# power_supply.net
KiCad netlist of a schematic drawn in Altium Designer
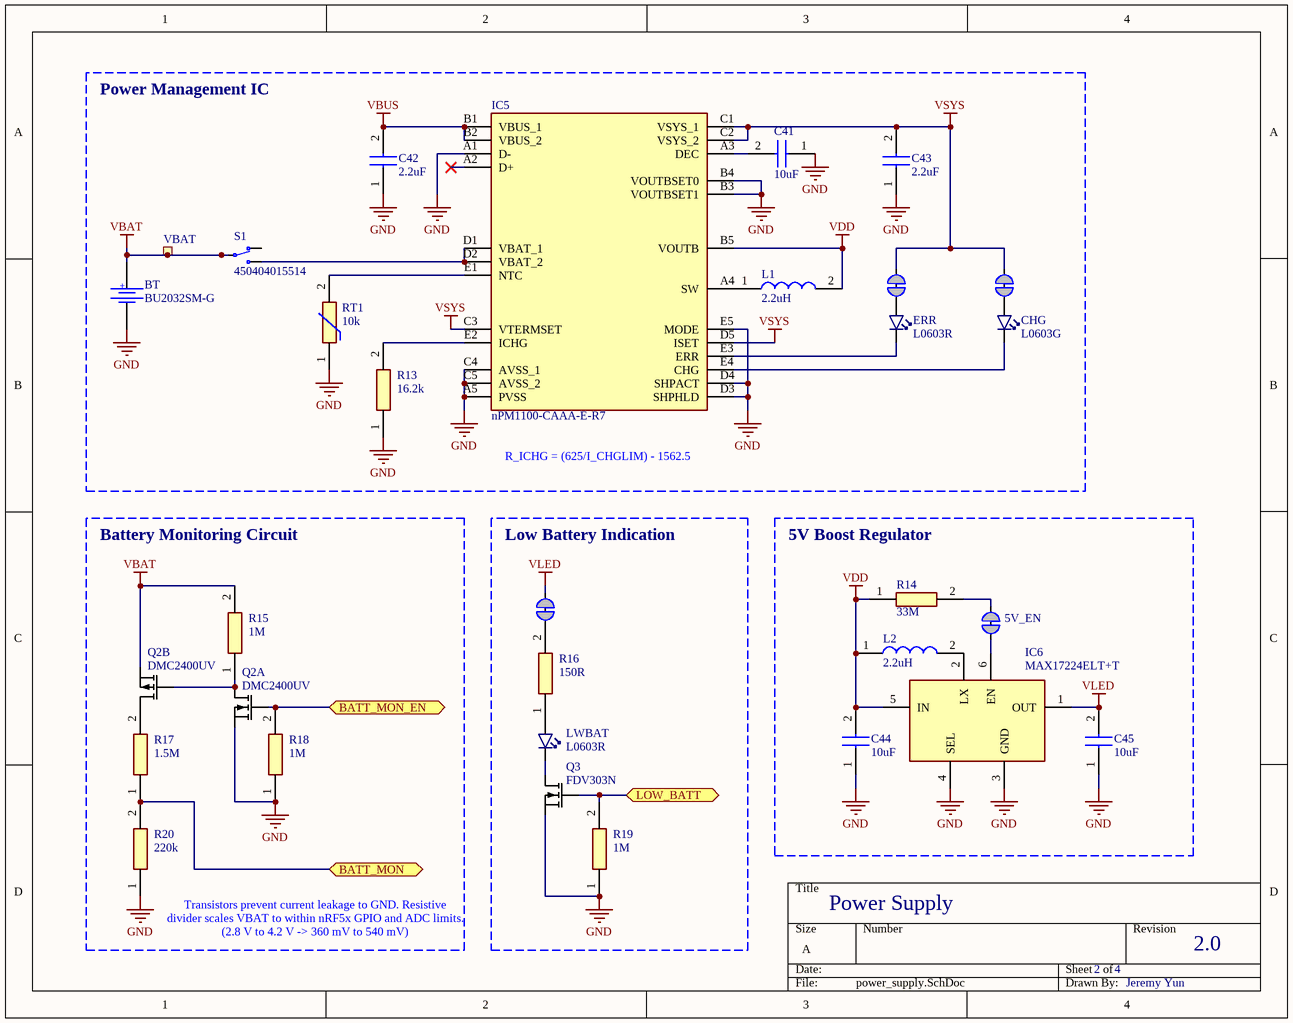
[diagram p0: power_supply.SchDoc]

(export (version "E")
  (design (tool "Eeschema 10.0.6"))
  (components
    (comp (ref "5V_EN")
      (value "Solderbridge")
      (footprint "Solderbridge_Shorted")
      (description "Shorted Solderbridge")
      (fields
        (field (name "PART NUMBER") "Solderbridge Shorted")
        (field (name "MANUFACTURER") "N.A.")
        (field (name "PUBLISHER") "Nordic Semiconductor")
        (field (name "AUTHOR") "rsk")
      )
      (libsource (lib "V2_wearable") (part "Solderbridge Shorted"))
    )
    (comp (ref "BT")
      (value "BU2032SM-G")
      (footprint "V2_wearable:BAT_BU2032SM-G")
      (description "BATTERY HOLDER COIN 20MM SMD")
      (fields (field (name "MF") "MPD"))
      (libsource (lib "V2_wearable") (part "BU2032SM-G"))
    )
    (comp (ref "C41")
      (value "10uF")
      (footprint "V2_wearable:CAPC1005X55N")
      (description "Capacitor 10uF X5R Ceramic")
      (fields
        (field (name "MANUFACTURER_PART_NUMBER") "GRM155R60J106ME05D")
        (field (name "MOUSER PART NUMBER") "81-GRM155R60J106M05D")
      )
      (libsource (lib "*") (part "GRM155R60J106ME05D"))
    )
    (comp (ref "C42")
      (value "2.2uF")
      (footprint "V2_wearable:CAPC0603X33N")
      (description "Capacitor")
      (fields
        (field (name "MANUFACTURER_PART_NUMBER") "GRM033R60J225ME47D")
        (field (name "MOUSER PART NUMBER") "81-GRM033R60J225ME7D")
      )
      (libsource (lib "*") (part "GRM033R60J225ME47D"))
    )
    (comp (ref "C43")
      (value "2.2uF")
      (footprint "V2_wearable:CAPC0603X33N")
      (description "Capacitor")
      (fields
        (field (name "MANUFACTURER_PART_NUMBER") "GRM033R60J225ME47D")
        (field (name "MOUSER PART NUMBER") "81-GRM033R60J225ME7D")
      )
      (libsource (lib "*") (part "GRM033R60J225ME47D"))
    )
    (comp (ref "C44")
      (value "10uF")
      (footprint "V2_wearable:CAPC1005X55N")
      (description "Capacitor 10uF X5R Ceramic")
      (fields
        (field (name "MANUFACTURER_PART_NUMBER") "GRM155R60J106ME05D")
        (field (name "MOUSER PART NUMBER") "81-GRM155R60J106M05D")
      )
      (libsource (lib "*") (part "GRM155R60J106ME05D"))
    )
    (comp (ref "C45")
      (value "10uF")
      (footprint "V2_wearable:CAPC1005X55N")
      (description "Capacitor 10uF X5R Ceramic")
      (fields
        (field (name "MANUFACTURER_PART_NUMBER") "GRM155R60J106ME05D")
        (field (name "MOUSER PART NUMBER") "81-GRM155R60J106M05D")
      )
      (libsource (lib "*") (part "GRM155R60J106ME05D"))
    )
    (comp (ref "CHG")
      (value "L0603G")
      (footprint "LED_0603_G")
      (description "LED, Green, 0603, 573nm, Vf=2.0V, 24mcd, - 40 to +85°C")
      (fields
        (field (name "PART NUMBER") "VS 25C7M5")
        (field (name "MANUFACTURER") "Victory Electronics")
        (field (name "AUTHOR") "rsk")
      )
      (libsource (lib "V2_wearable") (part "VS 25C7M5"))
    )
    (comp (ref "ERR")
      (value "L0603R")
      (footprint "V2_wearable:LEDC1608X80N")
      (description "LED")
      (fields
        (field (name "MANUFACTURER_PART_NUMBER") "LS Q976-NR-1")
        (field (name "MOUSER PART NUMBER") "720-LSQ976-NR-1")
      )
      (libsource (lib "V2_wearable") (part "LS_Q976-NR-1"))
    )
    (comp (ref "IC5")
      (value "nPM1100-CAAA-E-R7")
      (footprint "V2_wearable:BGA25C40P5X5_208X208X52")
      (description "Integrated Circuit")
      (fields
        (field (name "MOUSER PART NUMBER") "949-NPM1100-CAAA-R7")
        (field (name "ARROW PART NUMBER") "NPM1100-CAAA-E-R7")
      )
      (libsource (lib "V2_wearable") (part "nPM1100-CAAA-E-R7"))
    )
    (comp (ref "IC6")
      (value "MAX17224ELT+T")
      (footprint "V2_wearable:MAX17224ELTT")
      (description "Integrated Circuit")
      (fields (field (name "MOUSER PART NUMBER") "700-MAX17224ELT+T"))
      (libsource (lib "V2_wearable") (part "MAX17224ELT+T"))
    )
    (comp (ref "L1")
      (value "2.2uH")
      (footprint "DFE201210S1R0MP2")
      (description "Inductor")
      (fields
        (field (name "MANUFACTURER_PART_NUMBER") "DFE201210U-2R2M=P2")
        (field (name "MOUSER PART NUMBER") "81-DFE201210U-2R2MP2")
      )
      (libsource (lib "V2_wearable") (part "DFE201210U-2R2M=P2"))
    )
    (comp (ref "L2")
      (value "2.2uH")
      (footprint "LQM2HPZ3R3MJ0B")
      (description "Inductor")
      (fields
        (field (name "MANUFACTURER_PART_NUMBER") "LQM2HPN2R2MJ0L")
        (field (name "MOUSER PART NUMBER") "81-LQM2HPN2R2MJ0L")
      )
      (libsource (lib "V2_wearable") (part "LQM2HPN2R2MJ0L"))
    )
    (comp (ref "LWBAT")
      (value "L0603R")
      (footprint "V2_wearable:LEDC1608X80N")
      (description "LED")
      (fields
        (field (name "MANUFACTURER_PART_NUMBER") "LS Q976-NR-1")
        (field (name "MOUSER PART NUMBER") "720-LSQ976-NR-1")
      )
      (libsource (lib "V2_wearable") (part "LS_Q976-NR-1"))
    )
    (comp (ref "Q2")
      (value "DMC2400UV")
      (footprint "V2_wearable:SOTFL50P162X60-6N")
      (description "Transistor")
      (libsource (lib "V2_wearable") (part "DMC2400UV"))
    )
    (comp (ref "Q3")
      (value "FDV303N")
      (footprint "V2_wearable:SOT96P237X111-3N")
      (description "MOSFET (N-Channel)")
      (fields (field (name "MOUSER PART NUMBER") "512-FDV303N"))
      (libsource (lib "V2_wearable") (part "FDV303N"))
    )
    (comp (ref "R13")
      (value "16.2k")
      (footprint "V2_wearable:RESC1608X55N")
      (description "Resistor")
      (fields
        (field (name "MANUFACTURER_PART_NUMBER") "RC0603FR-0716K2L")
        (field (name "MOUSER PART NUMBER") "603-RC0603FR-0716K2L")
      )
      (libsource (lib "*") (part "RC0603FR-0716K2L"))
    )
    (comp (ref "R14")
      (value "33M")
      (footprint "RESC1005X40N")
      (description "Resistor")
      (fields (field (name "MANUFACTURER_PART_NUMBER") "HMC0402JT33M0"))
      (libsource (lib "V2_wearable") (part "HMC0402JT33M0"))
    )
    (comp (ref "R15")
      (value "1M")
      (footprint "V2_wearable:RESC1608X55N")
      (description "Resistor")
      (fields
        (field (name "MANUFACTURER_PART_NUMBER") "ERJ-3EKF1004V")
        (field (name "MOUSER PART NUMBER") "667-ERJ-3EKF1004V")
      )
      (libsource (lib "V2_wearable") (part "ERJ-3EKF1004V"))
    )
    (comp (ref "R16")
      (value "150R")
      (footprint "V2_wearable:ERJ2RKD1004X")
      (description "Resistor")
      (fields
        (field (name "MANUFACTURER_PART_NUMBER") "ERJ-2RKF1500X")
        (field (name "MOUSER PART NUMBER") "667-ERJ-2RKF1500X")
      )
      (libsource (lib "*") (part "ERJ-2RKF1500X"))
    )
    (comp (ref "R17")
      (value "1.5M")
      (footprint "V2_wearable:ERJ2RKD1004X")
      (description "Resistor")
      (fields
        (field (name "MANUFACTURER_PART_NUMBER") "ERJ-2GEJ155X")
        (field (name "MOUSER PART NUMBER") "667-ERJ-2GEJ155X")
      )
      (libsource (lib "*") (part "ERJ-2GEJ155X"))
    )
    (comp (ref "R18")
      (value "1M")
      (footprint "V2_wearable:RESC1608X55N")
      (description "Resistor")
      (fields
        (field (name "MANUFACTURER_PART_NUMBER") "ERJ-3EKF1004V")
        (field (name "MOUSER PART NUMBER") "667-ERJ-3EKF1004V")
      )
      (libsource (lib "V2_wearable") (part "ERJ-3EKF1004V"))
    )
    (comp (ref "R19")
      (value "1M")
      (footprint "V2_wearable:RESC1608X55N")
      (description "Resistor")
      (fields
        (field (name "MANUFACTURER_PART_NUMBER") "ERJ-3EKF1004V")
        (field (name "MOUSER PART NUMBER") "667-ERJ-3EKF1004V")
      )
      (libsource (lib "V2_wearable") (part "ERJ-3EKF1004V"))
    )
    (comp (ref "R20")
      (value "220k")
      (footprint "V2_wearable:ERJ2RKD1004X")
      (description "Resistor")
      (fields
        (field (name "MANUFACTURER_PART_NUMBER") "ERJ-2GEJ224X")
        (field (name "MOUSER PART NUMBER") "667-ERJ-2GEJ224X")
      )
      (libsource (lib "*") (part "ERJ-2GEJ224X"))
    )
    (comp (ref "RT1")
      (value "10k")
      (footprint "ERTJZEG103FA")
      (description "NTC Thermistor 10k 0201 (0603 Metric)")
      (fields
        (field (name "MANUFACTURER_PART_NUMBER") "ERT-JZEG103FA")
        (field (name "MOUSER PART NUMBER") "667-ERT-JZEG103FA")
      )
      (libsource (lib "V2_wearable") (part "ERT-JZEG103FA"))
    )
    (comp (ref "S1")
      (value "450404015514")
      (footprint "V2_wearable:450404015514")
      (description "Switch")
      (fields (field (name "MOUSER PART NUMBER") "710-450404015514"))
      (libsource (lib "V2_wearable") (part "450404015514"))
    )
    (comp (ref "SB9")
      (value "Solderbridge")
      (footprint "Solderbridge_Shorted")
      (description "Shorted Solderbridge")
      (fields
        (field (name "PART NUMBER") "Solderbridge Shorted")
        (field (name "MANUFACTURER") "N.A.")
        (field (name "PUBLISHER") "Nordic Semiconductor")
        (field (name "AUTHOR") "rsk")
      )
      (libsource (lib "V2_wearable") (part "Solderbridge Shorted"))
    )
    (comp (ref "SB10")
      (value "Solderbridge")
      (footprint "Solderbridge_Shorted")
      (description "Shorted Solderbridge")
      (fields
        (field (name "PART NUMBER") "Solderbridge Shorted")
        (field (name "MANUFACTURER") "N.A.")
        (field (name "PUBLISHER") "Nordic Semiconductor")
        (field (name "AUTHOR") "rsk")
      )
      (libsource (lib "V2_wearable") (part "Solderbridge Shorted"))
    )
    (comp (ref "SB15")
      (value "Solderbridge")
      (footprint "Solderbridge_Shorted")
      (description "Shorted Solderbridge")
      (fields
        (field (name "PART NUMBER") "Solderbridge Shorted")
        (field (name "MANUFACTURER") "N.A.")
        (field (name "PUBLISHER") "Nordic Semiconductor")
        (field (name "AUTHOR") "rsk")
      )
      (libsource (lib "V2_wearable") (part "Solderbridge Shorted"))
    )
    (comp (ref "VBAT")
      (value "Ø1.0mm,SMD")
      (footprint "TP_SMD_D1.0mm")
      (description "1.0mm circular SMD testpad")
      (fields
        (field (name "PART NUMBER") "TP_SMD_Ø1.0MM")
        (field (name "MANUFACTURER") "Nordic Semiconductor")
        (field (name "PUBLISHER") "Nordic Semiconductor")
        (field (name "AUTHOR") "rsk")
      )
      (libsource (lib "V2_wearable") (part "TP_SMD_Ø1.0MM"))
    )
  )
  (nets
    (net (code "1") (name "/BATT_MON") (class "Default")
      (node (ref "R17") (pin "1") (pinfunction "1_1") (pintype "passive"))
      (node (ref "R20") (pin "2") (pinfunction "2_2") (pintype "passive"))
    )
    (net (code "2") (name "/BATT_MON_EN") (class "Default")
      (node (ref "Q2") (pin "2") (pinfunction "G1_2") (pintype "passive"))
      (node (ref "R18") (pin "2") (pinfunction "2_2") (pintype "passive"))
    )
    (net (code "3") (name "/LOW_BATT") (class "Default")
      (node (ref "Q3") (pin "1") (pinfunction "G_1") (pintype "passive"))
      (node (ref "R19") (pin "2") (pinfunction "2_2") (pintype "passive"))
    )
    (net (code "4") (name "GND") (class "Default")
      (node (ref "BT") (pin "NEG") (pinfunction "NEG_NEG") (pintype "passive"))
      (node (ref "C41") (pin "1") (pinfunction "1_1") (pintype "passive"))
      (node (ref "C42") (pin "1") (pinfunction "1_1") (pintype "passive"))
      (node (ref "C43") (pin "1") (pinfunction "1_1") (pintype "passive"))
      (node (ref "C44") (pin "1") (pinfunction "1_1") (pintype "passive"))
      (node (ref "C45") (pin "1") (pinfunction "1_1") (pintype "passive"))
      (node (ref "IC5") (pin "A1") (pinfunction "D-_A1") (pintype "passive"))
      (node (ref "IC5") (pin "A5") (pinfunction "PVSS_A5") (pintype "passive"))
      (node (ref "IC5") (pin "B3") (pinfunction "VOUTBSET1_B3") (pintype "passive"))
      (node (ref "IC5") (pin "B4") (pinfunction "VOUTBSET0_B4") (pintype "passive"))
      (node (ref "IC5") (pin "C4") (pinfunction "AVSS_1_C4") (pintype "passive"))
      (node (ref "IC5") (pin "C5") (pinfunction "AVSS_2_C5") (pintype "passive"))
      (node (ref "IC5") (pin "D3") (pinfunction "SHPHLD_D3") (pintype "passive"))
      (node (ref "IC5") (pin "D4") (pinfunction "SHPACT_D4") (pintype "passive"))
      (node (ref "IC5") (pin "E5") (pinfunction "MODE_E5") (pintype "passive"))
      (node (ref "IC6") (pin "3") (pinfunction "GND_3") (pintype "passive"))
      (node (ref "IC6") (pin "4") (pinfunction "SEL_4") (pintype "passive"))
      (node (ref "Q2") (pin "1") (pinfunction "S1_1") (pintype "passive"))
      (node (ref "Q3") (pin "2") (pinfunction "S_2") (pintype "passive"))
      (node (ref "R13") (pin "1") (pinfunction "1_1") (pintype "passive"))
      (node (ref "R18") (pin "1") (pinfunction "1_1") (pintype "passive"))
      (node (ref "R19") (pin "1") (pinfunction "1_1") (pintype "passive"))
      (node (ref "R20") (pin "1") (pinfunction "1_1") (pintype "passive"))
      (node (ref "RT1") (pin "1") (pinfunction "1_1") (pintype "passive"))
    )
    (net (code "5") (name "Net-(5V_EN-0)") (class "Default")
      (node (ref "5V_EN") (pin "1") (pinfunction "0_1") (pintype "passive"))
      (node (ref "IC6") (pin "6") (pinfunction "EN_6") (pintype "passive"))
    )
    (net (code "6") (name "Net-(5V_EN-1)") (class "Default")
      (node (ref "5V_EN") (pin "2") (pinfunction "1_2") (pintype "passive"))
      (node (ref "R14") (pin "2") (pinfunction "2_2") (pintype "passive"))
    )
    (net (code "7") (name "Net-(CHG-A)") (class "Default")
      (node (ref "CHG") (pin "2") (pinfunction "A_2") (pintype "passive"))
      (node (ref "SB10") (pin "1") (pinfunction "0_1") (pintype "passive"))
    )
    (net (code "8") (name "Net-(CHG-C)") (class "Default")
      (node (ref "CHG") (pin "1") (pinfunction "C_1") (pintype "passive"))
      (node (ref "IC5") (pin "E4") (pinfunction "CHG_E4") (pintype "passive"))
    )
    (net (code "9") (name "Net-(ERR-A)") (class "Default")
      (node (ref "ERR") (pin "2") (pinfunction "A_2") (pintype "passive"))
      (node (ref "SB9") (pin "1") (pinfunction "0_1") (pintype "passive"))
    )
    (net (code "10") (name "Net-(ERR-C)") (class "Default")
      (node (ref "ERR") (pin "1") (pinfunction "C_1") (pintype "passive"))
      (node (ref "IC5") (pin "E3") (pinfunction "ERR_E3") (pintype "passive"))
    )
    (net (code "11") (name "Net-(IC5-DEC)") (class "Default")
      (node (ref "C41") (pin "2") (pinfunction "2_2") (pintype "passive"))
      (node (ref "IC5") (pin "A3") (pinfunction "DEC_A3") (pintype "passive"))
    )
    (net (code "12") (name "Net-(IC5-ICHG)") (class "Default")
      (node (ref "IC5") (pin "E2") (pinfunction "ICHG_E2") (pintype "passive"))
      (node (ref "R13") (pin "2") (pinfunction "2_2") (pintype "passive"))
    )
    (net (code "13") (name "Net-(IC5-NTC)") (class "Default")
      (node (ref "IC5") (pin "E1") (pinfunction "NTC_E1") (pintype "passive"))
      (node (ref "RT1") (pin "2") (pinfunction "2_2") (pintype "passive"))
    )
    (net (code "14") (name "Net-(IC5-SW)") (class "Default")
      (node (ref "IC5") (pin "A4") (pinfunction "SW_A4") (pintype "passive"))
      (node (ref "L1") (pin "1") (pinfunction "1_1") (pintype "passive"))
    )
    (net (code "15") (name "Net-(IC5-VBAT_1)") (class "Default")
      (node (ref "IC5") (pin "D1") (pinfunction "VBAT_1_D1") (pintype "passive"))
      (node (ref "IC5") (pin "D2") (pinfunction "VBAT_2_D2") (pintype "passive"))
      (node (ref "S1") (pin "1") (pinfunction "N.O-1_1") (pintype "passive"))
    )
    (net (code "16") (name "Net-(IC6-LX)") (class "Default")
      (node (ref "IC6") (pin "2") (pinfunction "LX_2") (pintype "passive"))
      (node (ref "L2") (pin "2") (pinfunction "2_2") (pintype "passive"))
    )
    (net (code "17") (name "Net-(LWBAT-A)") (class "Default")
      (node (ref "LWBAT") (pin "2") (pinfunction "A_2") (pintype "passive"))
      (node (ref "R16") (pin "1") (pinfunction "1_1") (pintype "passive"))
    )
    (net (code "18") (name "Net-(LWBAT-C)") (class "Default")
      (node (ref "LWBAT") (pin "1") (pinfunction "C_1") (pintype "passive"))
      (node (ref "Q3") (pin "3") (pinfunction "D_3") (pintype "passive"))
    )
    (net (code "19") (name "Net-(Q2A-D1)") (class "Default")
      (node (ref "Q2") (pin "5") (pinfunction "G2_5") (pintype "passive"))
      (node (ref "Q2") (pin "6") (pinfunction "D1_6") (pintype "passive"))
      (node (ref "R15") (pin "1") (pinfunction "1_1") (pintype "passive"))
    )
    (net (code "20") (name "Net-(Q2B-D2)") (class "Default")
      (node (ref "Q2") (pin "3") (pinfunction "D2_3") (pintype "passive"))
      (node (ref "R17") (pin "2") (pinfunction "2_2") (pintype "passive"))
    )
    (net (code "21") (name "Net-(SB15-0)") (class "Default")
      (node (ref "R16") (pin "2") (pinfunction "2_2") (pintype "passive"))
      (node (ref "SB15") (pin "1") (pinfunction "0_1") (pintype "passive"))
    )
    (net (code "22") (name "VBAT") (class "Default")
      (node (ref "BT") (pin "POS") (pinfunction "POS_POS") (pintype "passive"))
      (node (ref "Q2") (pin "4") (pinfunction "S2_4") (pintype "passive"))
      (node (ref "R15") (pin "2") (pinfunction "2_2") (pintype "passive"))
      (node (ref "S1") (pin "2") (pinfunction "COM-1_2") (pintype "passive"))
      (node (ref "VBAT") (pin "1") (pinfunction "1_1") (pintype "passive"))
    )
    (net (code "23") (name "VBUS") (class "Default")
      (node (ref "C42") (pin "2") (pinfunction "2_2") (pintype "passive"))
      (node (ref "IC5") (pin "B1") (pinfunction "VBUS_1_B1") (pintype "passive"))
      (node (ref "IC5") (pin "B2") (pinfunction "VBUS_2_B2") (pintype "passive"))
    )
    (net (code "24") (name "VDD") (class "Default")
      (node (ref "C44") (pin "2") (pinfunction "2_2") (pintype "passive"))
      (node (ref "IC5") (pin "B5") (pinfunction "VOUTB_B5") (pintype "passive"))
      (node (ref "IC6") (pin "5") (pinfunction "IN_5") (pintype "passive"))
      (node (ref "L1") (pin "2") (pinfunction "2_2") (pintype "passive"))
      (node (ref "L2") (pin "1") (pinfunction "1_1") (pintype "passive"))
      (node (ref "R14") (pin "1") (pinfunction "1_1") (pintype "passive"))
    )
    (net (code "25") (name "VLED") (class "Default")
      (node (ref "C45") (pin "2") (pinfunction "2_2") (pintype "passive"))
      (node (ref "IC6") (pin "1") (pinfunction "OUT_1") (pintype "passive"))
      (node (ref "SB15") (pin "2") (pinfunction "1_2") (pintype "passive"))
    )
    (net (code "26") (name "VSYS") (class "Default")
      (node (ref "C43") (pin "2") (pinfunction "2_2") (pintype "passive"))
      (node (ref "IC5") (pin "C1") (pinfunction "VSYS_1_C1") (pintype "passive"))
      (node (ref "IC5") (pin "C2") (pinfunction "VSYS_2_C2") (pintype "passive"))
      (node (ref "IC5") (pin "C3") (pinfunction "VTERMSET_C3") (pintype "passive"))
      (node (ref "IC5") (pin "D5") (pinfunction "ISET_D5") (pintype "passive"))
      (node (ref "SB10") (pin "2") (pinfunction "1_2") (pintype "passive"))
      (node (ref "SB9") (pin "2") (pinfunction "1_2") (pintype "passive"))
    )
    (net (code "27") (name "unconnected-(IC5-D+-PadA2)") (class "Default")
      (node (ref "IC5") (pin "A2") (pinfunction "D+_A2") (pintype "passive+no_connect"))
    )
    (net (code "28") (name "unconnected-(S1-N.C-1-Pad3)") (class "Default")
      (node (ref "S1") (pin "3") (pinfunction "N.C-1_3") (pintype "passive"))
    )
  )
)
